# Leak_and_Level_Sense.net
KiCad netlist of a schematic drawn in Altium Designer
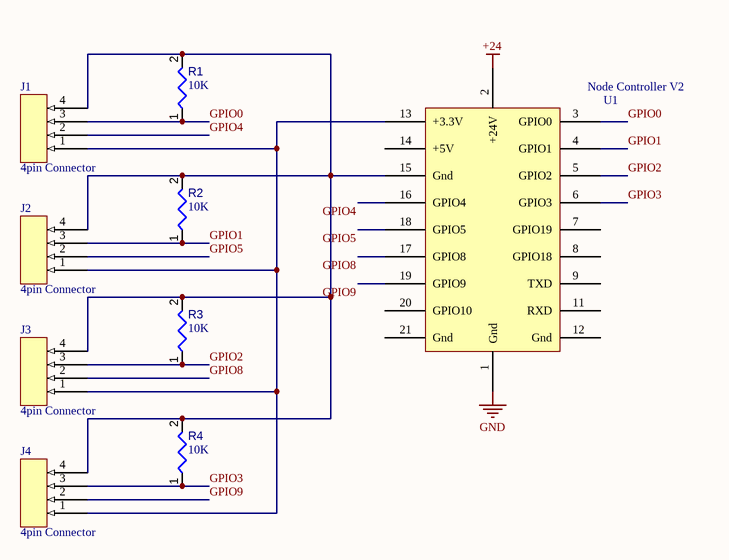
[diagram p0: Leak and Level Sense.SchDoc]

(export (version "E")
  (design (tool "Eeschema 10.0.6"))
  (components
    (comp (ref "J1")
      (value "4pin Connector")
      (libsource (lib "Leak and Level Sense") (part "4pin Connector"))
    )
    (comp (ref "J2")
      (value "4pin Connector")
      (libsource (lib "Leak and Level Sense") (part "4pin Connector"))
    )
    (comp (ref "J3")
      (value "4pin Connector")
      (libsource (lib "Leak and Level Sense") (part "4pin Connector"))
    )
    (comp (ref "J4")
      (value "4pin Connector")
      (libsource (lib "Leak and Level Sense") (part "4pin Connector"))
    )
    (comp (ref "R1")
      (value "10K")
      (footprint "RESC0402(1005)_L")
      (description "Chip Resistor, 2,2 kOhms, +/-5 %, 63 mW, -55 to 155 degC, 0402")
      (fields (field (name "POWER") "63mW") (field (name "TOLERANCE") "5%"))
      (libsource (lib "Leak and Level Sense") (part "RES-2"))
    )
    (comp (ref "R2")
      (value "10K")
      (footprint "RESC0402(1005)_L")
      (description "Chip Resistor, 2,2 kOhms, +/-5 %, 63 mW, -55 to 155 degC, 0402")
      (fields (field (name "POWER") "63mW") (field (name "TOLERANCE") "5%"))
      (libsource (lib "Leak and Level Sense") (part "RES-2"))
    )
    (comp (ref "R3")
      (value "10K")
      (footprint "RESC0402(1005)_L")
      (description "Chip Resistor, 2,2 kOhms, +/-5 %, 63 mW, -55 to 155 degC, 0402")
      (fields (field (name "POWER") "63mW") (field (name "TOLERANCE") "5%"))
      (libsource (lib "Leak and Level Sense") (part "RES-2"))
    )
    (comp (ref "R4")
      (value "10K")
      (footprint "RESC0402(1005)_L")
      (description "Chip Resistor, 2,2 kOhms, +/-5 %, 63 mW, -55 to 155 degC, 0402")
      (fields (field (name "POWER") "63mW") (field (name "TOLERANCE") "5%"))
      (libsource (lib "Leak and Level Sense") (part "RES-2"))
    )
    (comp (ref "U1")
      (value "Node Controller V2")
      (libsource (lib "Leak and Level Sense") (part "Node Controller V2"))
    )
  )
  (nets
    (net (code "1") (name "+24") (class "Default")
      (node (ref "U1") (pin "2") (pinfunction "+24V_2") (pintype "passive"))
    )
    (net (code "2") (name "/GPIO0") (class "Default")
      (node (ref "J1") (pin "3") (pintype "input"))
      (node (ref "R1") (pin "1") (pinfunction "1_1") (pintype "passive"))
      (node (ref "U1") (pin "3") (pinfunction "GPIO0_3") (pintype "passive"))
    )
    (net (code "3") (name "/GPIO1") (class "Default")
      (node (ref "J2") (pin "3") (pintype "input"))
      (node (ref "R2") (pin "1") (pinfunction "1_1") (pintype "passive"))
      (node (ref "U1") (pin "4") (pinfunction "GPIO1_4") (pintype "passive"))
    )
    (net (code "4") (name "/GPIO2") (class "Default")
      (node (ref "J3") (pin "3") (pintype "input"))
      (node (ref "R3") (pin "1") (pinfunction "1_1") (pintype "passive"))
      (node (ref "U1") (pin "5") (pinfunction "GPIO2_5") (pintype "passive"))
    )
    (net (code "5") (name "/GPIO3") (class "Default")
      (node (ref "J4") (pin "3") (pintype "input"))
      (node (ref "R4") (pin "1") (pinfunction "1_1") (pintype "passive"))
      (node (ref "U1") (pin "6") (pinfunction "GPIO3_6") (pintype "passive"))
    )
    (net (code "6") (name "/GPIO4") (class "Default")
      (node (ref "J1") (pin "2") (pintype "input"))
      (node (ref "U1") (pin "16") (pinfunction "GPIO4_16") (pintype "passive"))
    )
    (net (code "7") (name "/GPIO5") (class "Default")
      (node (ref "J2") (pin "2") (pintype "input"))
      (node (ref "U1") (pin "18") (pinfunction "GPIO5_18") (pintype "passive"))
    )
    (net (code "8") (name "/GPIO8") (class "Default")
      (node (ref "J3") (pin "2") (pintype "input"))
      (node (ref "U1") (pin "17") (pinfunction "GPIO8_17") (pintype "passive"))
    )
    (net (code "9") (name "/GPIO9") (class "Default")
      (node (ref "J4") (pin "2") (pintype "input"))
      (node (ref "U1") (pin "19") (pinfunction "GPIO9_19") (pintype "passive"))
    )
    (net (code "10") (name "GND") (class "Default")
      (node (ref "U1") (pin "1") (pinfunction "Gnd_1") (pintype "passive"))
    )
    (net (code "11") (name "Net-(J1-Pad4)") (class "Default")
      (node (ref "J1") (pin "4") (pintype "input"))
      (node (ref "J2") (pin "4") (pintype "input"))
      (node (ref "J3") (pin "4") (pintype "input"))
      (node (ref "J4") (pin "4") (pintype "input"))
      (node (ref "R1") (pin "2") (pinfunction "2_2") (pintype "passive"))
      (node (ref "R2") (pin "2") (pinfunction "2_2") (pintype "passive"))
      (node (ref "R3") (pin "2") (pinfunction "2_2") (pintype "passive"))
      (node (ref "R4") (pin "2") (pinfunction "2_2") (pintype "passive"))
      (node (ref "U1") (pin "15") (pinfunction "Gnd_15") (pintype "passive"))
    )
    (net (code "12") (name "Net-(U1-+3.3V)") (class "Default")
      (node (ref "J1") (pin "1") (pintype "input"))
      (node (ref "J2") (pin "1") (pintype "input"))
      (node (ref "J3") (pin "1") (pintype "input"))
      (node (ref "J4") (pin "1") (pintype "input"))
      (node (ref "U1") (pin "13") (pinfunction "+3.3V_13") (pintype "passive"))
    )
    (net (code "13") (name "unconnected-(U1-+5V-Pad14)") (class "Default")
      (node (ref "U1") (pin "14") (pinfunction "+5V_14") (pintype "passive"))
    )
    (net (code "14") (name "unconnected-(U1-GPIO10-Pad20)") (class "Default")
      (node (ref "U1") (pin "20") (pinfunction "GPIO10_20") (pintype "passive"))
    )
    (net (code "15") (name "unconnected-(U1-GPIO18-Pad8)") (class "Default")
      (node (ref "U1") (pin "8") (pinfunction "GPIO18_8") (pintype "passive"))
    )
    (net (code "16") (name "unconnected-(U1-GPIO19-Pad7)") (class "Default")
      (node (ref "U1") (pin "7") (pinfunction "GPIO19_7") (pintype "passive"))
    )
    (net (code "17") (name "unconnected-(U1-Gnd-Pad12)") (class "Default")
      (node (ref "U1") (pin "12") (pinfunction "Gnd_12") (pintype "passive"))
    )
    (net (code "18") (name "unconnected-(U1-Gnd-Pad21)") (class "Default")
      (node (ref "U1") (pin "21") (pinfunction "Gnd_21") (pintype "passive"))
    )
    (net (code "19") (name "unconnected-(U1-RXD-Pad11)") (class "Default")
      (node (ref "U1") (pin "11") (pinfunction "RXD_11") (pintype "passive"))
    )
    (net (code "20") (name "unconnected-(U1-TXD-Pad9)") (class "Default")
      (node (ref "U1") (pin "9") (pinfunction "TXD_9") (pintype "passive"))
    )
  )
)
